# HyperRAM.net
KiCad netlist of a schematic drawn in Altium Designer
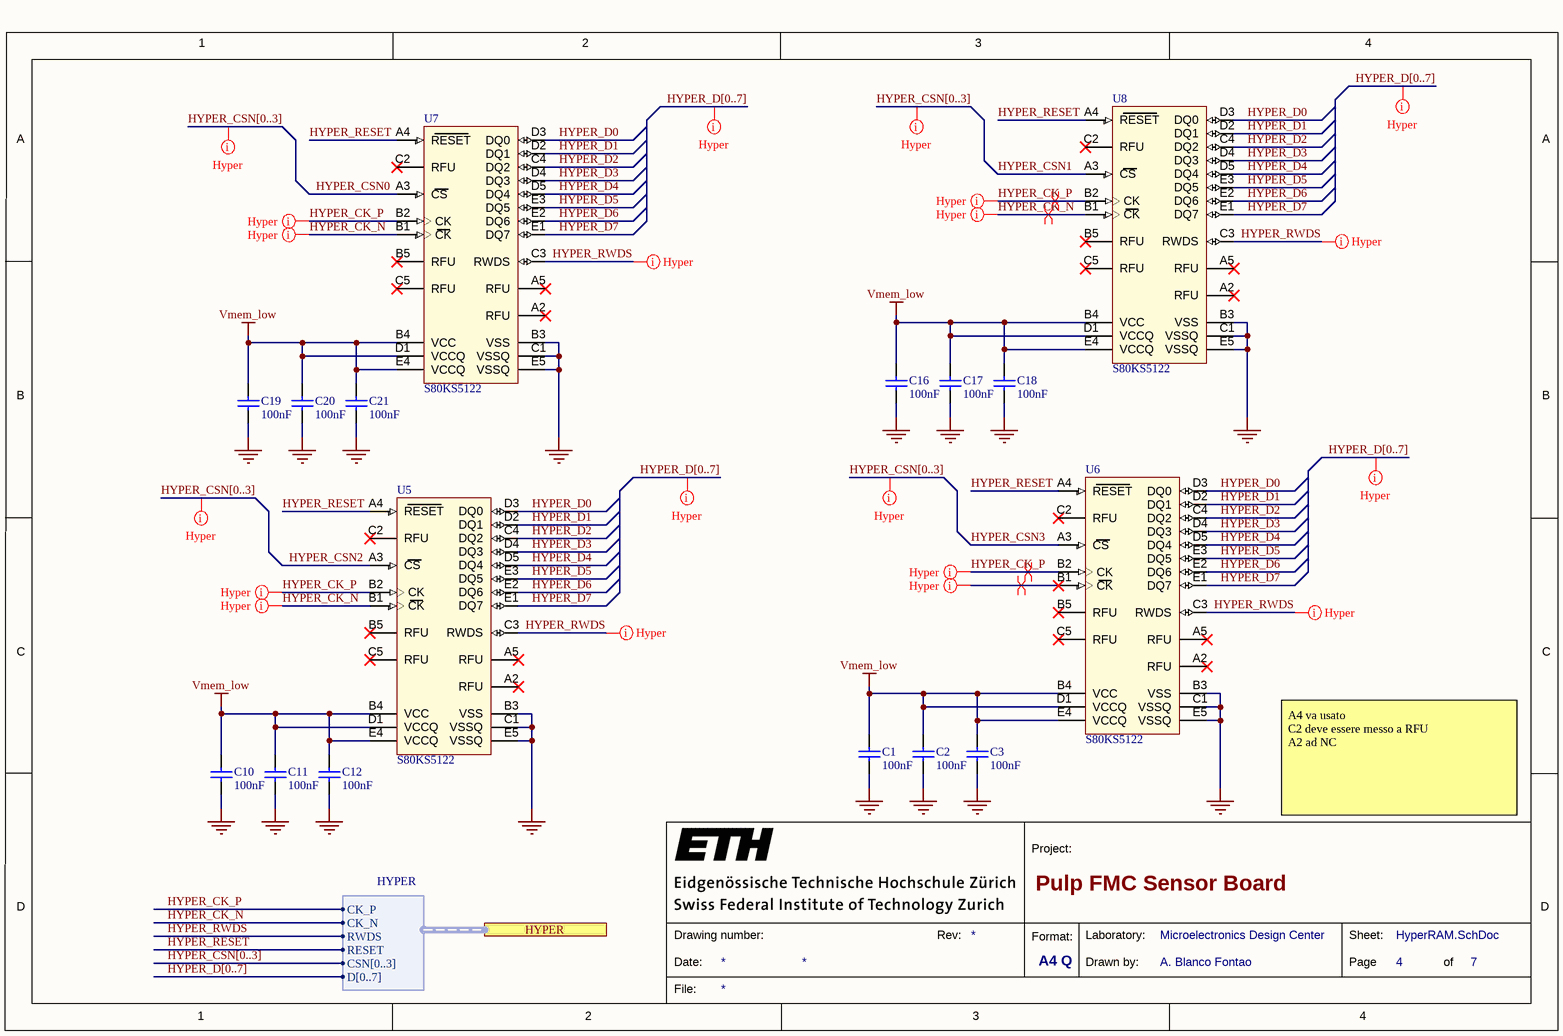
[diagram p0: HyperRAM.SchDoc]

(export (version "E")
  (design (tool "Eeschema 10.0.6"))
  (components
    (comp (ref "C1")
      (value "100nF")
      (footprint "CAPC0603(1608)100_N")
      (description "CAP 100nF 25V ±10% 0603 (1608 Metric) Thickness 1mm SMD")
      (fields (field (name "TOLERANCE") "Â±10%") (field (name "Comment") "CAP 100nF 25V 0603(1608)"))
      (libsource (lib "Altium Content Vault") (part "CMP-1035-02588-1"))
    )
    (comp (ref "C2")
      (value "100nF")
      (footprint "CAPC0603(1608)100_N")
      (description "CAP 100nF 25V ±10% 0603 (1608 Metric) Thickness 1mm SMD")
      (fields (field (name "TOLERANCE") "Â±10%") (field (name "Comment") "CAP 100nF 25V 0603(1608)"))
      (libsource (lib "Altium Content Vault") (part "CMP-1035-02588-1"))
    )
    (comp (ref "C3")
      (value "100nF")
      (footprint "CAPC0603(1608)100_N")
      (description "CAP 100nF 25V ±10% 0603 (1608 Metric) Thickness 1mm SMD")
      (fields (field (name "TOLERANCE") "Â±10%") (field (name "Comment") "CAP 100nF 25V 0603(1608)"))
      (libsource (lib "Altium Content Vault") (part "CMP-1035-02588-1"))
    )
    (comp (ref "C10")
      (value "100nF")
      (footprint "CAPC0603(1608)100_N")
      (description "CAP 100nF 25V ±10% 0603 (1608 Metric) Thickness 1mm SMD")
      (fields (field (name "TOLERANCE") "Â±10%") (field (name "Comment") "CAP 100nF 25V 0603(1608)"))
      (libsource (lib "Altium Content Vault") (part "CMP-1035-02588-1"))
    )
    (comp (ref "C11")
      (value "100nF")
      (footprint "CAPC0603(1608)100_N")
      (description "CAP 100nF 25V ±10% 0603 (1608 Metric) Thickness 1mm SMD")
      (fields (field (name "TOLERANCE") "Â±10%") (field (name "Comment") "CAP 100nF 25V 0603(1608)"))
      (libsource (lib "Altium Content Vault") (part "CMP-1035-02588-1"))
    )
    (comp (ref "C12")
      (value "100nF")
      (footprint "CAPC0603(1608)100_N")
      (description "CAP 100nF 25V ±10% 0603 (1608 Metric) Thickness 1mm SMD")
      (fields (field (name "TOLERANCE") "Â±10%") (field (name "Comment") "CAP 100nF 25V 0603(1608)"))
      (libsource (lib "Altium Content Vault") (part "CMP-1035-02588-1"))
    )
    (comp (ref "C16")
      (value "100nF")
      (footprint "CAPC0603(1608)100_N")
      (description "CAP 100nF 25V ±10% 0603 (1608 Metric) Thickness 1mm SMD")
      (fields (field (name "TOLERANCE") "Â±10%") (field (name "Comment") "CAP 100nF 25V 0603(1608)"))
      (libsource (lib "Altium Content Vault") (part "CMP-1035-02588-1"))
    )
    (comp (ref "C17")
      (value "100nF")
      (footprint "CAPC0603(1608)100_N")
      (description "CAP 100nF 25V ±10% 0603 (1608 Metric) Thickness 1mm SMD")
      (fields (field (name "TOLERANCE") "Â±10%") (field (name "Comment") "CAP 100nF 25V 0603(1608)"))
      (libsource (lib "Altium Content Vault") (part "CMP-1035-02588-1"))
    )
    (comp (ref "C18")
      (value "100nF")
      (footprint "CAPC0603(1608)100_N")
      (description "CAP 100nF 25V ±10% 0603 (1608 Metric) Thickness 1mm SMD")
      (fields (field (name "TOLERANCE") "Â±10%") (field (name "Comment") "CAP 100nF 25V 0603(1608)"))
      (libsource (lib "Altium Content Vault") (part "CMP-1035-02588-1"))
    )
    (comp (ref "C19")
      (value "100nF")
      (footprint "CAPC0603(1608)100_N")
      (description "CAP 100nF 25V ±10% 0603 (1608 Metric) Thickness 1mm SMD")
      (fields (field (name "TOLERANCE") "Â±10%") (field (name "Comment") "CAP 100nF 25V 0603(1608)"))
      (libsource (lib "Altium Content Vault") (part "CMP-1035-02588-1"))
    )
    (comp (ref "C20")
      (value "100nF")
      (footprint "CAPC0603(1608)100_N")
      (description "CAP 100nF 25V ±10% 0603 (1608 Metric) Thickness 1mm SMD")
      (fields (field (name "TOLERANCE") "Â±10%") (field (name "Comment") "CAP 100nF 25V 0603(1608)"))
      (libsource (lib "Altium Content Vault") (part "CMP-1035-02588-1"))
    )
    (comp (ref "C21")
      (value "100nF")
      (footprint "CAPC0603(1608)100_N")
      (description "CAP 100nF 25V ±10% 0603 (1608 Metric) Thickness 1mm SMD")
      (fields (field (name "TOLERANCE") "Â±10%") (field (name "Comment") "CAP 100nF 25V 0603(1608)"))
      (libsource (lib "Altium Content Vault") (part "CMP-1035-02588-1"))
    )
    (comp (ref "U5")
      (value "S80KS5122")
      (footprint "FBGA24_A-130")
      (description "512 Mb: HYPERRAM™ self-refresh dynamic\r\nRAM (DRAM) with HYPERBUS™ interface\r\n1.8 V")
      (libsource (lib "hyperRAM") (part "S80KS5122"))
    )
    (comp (ref "U6")
      (value "S80KS5122")
      (footprint "FBGA24_A-130")
      (description "512 Mb: HYPERRAM™ self-refresh dynamic\r\nRAM (DRAM) with HYPERBUS™ interface\r\n1.8 V")
      (libsource (lib "hyperRAM") (part "S80KS5122"))
    )
    (comp (ref "U7")
      (value "S80KS5122")
      (footprint "FBGA24_A-130")
      (description "512 Mb: HYPERRAM™ self-refresh dynamic\r\nRAM (DRAM) with HYPERBUS™ interface\r\n1.8 V")
      (libsource (lib "hyperRAM") (part "S80KS5122"))
    )
    (comp (ref "U8")
      (value "S80KS5122")
      (footprint "FBGA24_A-130")
      (description "512 Mb: HYPERRAM™ self-refresh dynamic\r\nRAM (DRAM) with HYPERBUS™ interface\r\n1.8 V")
      (libsource (lib "hyperRAM") (part "S80KS5122"))
    )
  )
  (nets
    (net (code "2") (name "/HYPER_CK_N") (class "Default")
      (node (ref "U5") (pin "B1") (pinfunction "CK_B1") (pintype "input"))
      (node (ref "U7") (pin "B1") (pinfunction "CK_B1") (pintype "input"))
      (node (ref "U8") (pin "B1") (pinfunction "CK_B1") (pintype "input"))
    )
    (net (code "3") (name "/HYPER_CK_P") (class "Default")
      (node (ref "U5") (pin "B2") (pinfunction "CK_B2") (pintype "input"))
      (node (ref "U6") (pin "B2") (pinfunction "CK_B2") (pintype "input"))
      (node (ref "U7") (pin "B2") (pinfunction "CK_B2") (pintype "input"))
      (node (ref "U8") (pin "B2") (pinfunction "CK_B2") (pintype "input"))
    )
    (net (code "4") (name "/HYPER_CSN0") (class "Default")
      (node (ref "U7") (pin "A3") (pinfunction "CS_A3") (pintype "input"))
    )
    (net (code "5") (name "/HYPER_CSN1") (class "Default")
      (node (ref "U8") (pin "A3") (pinfunction "CS_A3") (pintype "input"))
    )
    (net (code "6") (name "/HYPER_CSN2") (class "Default")
      (node (ref "U5") (pin "A3") (pinfunction "CS_A3") (pintype "input"))
    )
    (net (code "7") (name "/HYPER_CSN3") (class "Default")
      (node (ref "U6") (pin "A3") (pinfunction "CS_A3") (pintype "input"))
    )
    (net (code "9") (name "/HYPER_D0") (class "Default")
      (node (ref "U5") (pin "D3") (pinfunction "DQ0_D3") (pintype "bidirectional"))
      (node (ref "U6") (pin "D3") (pinfunction "DQ0_D3") (pintype "bidirectional"))
      (node (ref "U7") (pin "D3") (pinfunction "DQ0_D3") (pintype "bidirectional"))
      (node (ref "U8") (pin "D3") (pinfunction "DQ0_D3") (pintype "bidirectional"))
    )
    (net (code "10") (name "/HYPER_D1") (class "Default")
      (node (ref "U5") (pin "D2") (pinfunction "DQ1_D2") (pintype "bidirectional"))
      (node (ref "U6") (pin "D2") (pinfunction "DQ1_D2") (pintype "bidirectional"))
      (node (ref "U7") (pin "D2") (pinfunction "DQ1_D2") (pintype "bidirectional"))
      (node (ref "U8") (pin "D2") (pinfunction "DQ1_D2") (pintype "bidirectional"))
    )
    (net (code "11") (name "/HYPER_D2") (class "Default")
      (node (ref "U5") (pin "C4") (pinfunction "DQ2_C4") (pintype "bidirectional"))
      (node (ref "U6") (pin "C4") (pinfunction "DQ2_C4") (pintype "bidirectional"))
      (node (ref "U7") (pin "C4") (pinfunction "DQ2_C4") (pintype "bidirectional"))
      (node (ref "U8") (pin "C4") (pinfunction "DQ2_C4") (pintype "bidirectional"))
    )
    (net (code "12") (name "/HYPER_D3") (class "Default")
      (node (ref "U5") (pin "D4") (pinfunction "DQ3_D4") (pintype "bidirectional"))
      (node (ref "U6") (pin "D4") (pinfunction "DQ3_D4") (pintype "bidirectional"))
      (node (ref "U7") (pin "D4") (pinfunction "DQ3_D4") (pintype "bidirectional"))
      (node (ref "U8") (pin "D4") (pinfunction "DQ3_D4") (pintype "bidirectional"))
    )
    (net (code "13") (name "/HYPER_D4") (class "Default")
      (node (ref "U5") (pin "D5") (pinfunction "DQ4_D5") (pintype "bidirectional"))
      (node (ref "U6") (pin "D5") (pinfunction "DQ4_D5") (pintype "bidirectional"))
      (node (ref "U7") (pin "D5") (pinfunction "DQ4_D5") (pintype "bidirectional"))
      (node (ref "U8") (pin "D5") (pinfunction "DQ4_D5") (pintype "bidirectional"))
    )
    (net (code "14") (name "/HYPER_D5") (class "Default")
      (node (ref "U5") (pin "E3") (pinfunction "DQ5_E3") (pintype "bidirectional"))
      (node (ref "U6") (pin "E3") (pinfunction "DQ5_E3") (pintype "bidirectional"))
      (node (ref "U7") (pin "E3") (pinfunction "DQ5_E3") (pintype "bidirectional"))
      (node (ref "U8") (pin "E3") (pinfunction "DQ5_E3") (pintype "bidirectional"))
    )
    (net (code "15") (name "/HYPER_D6") (class "Default")
      (node (ref "U5") (pin "E2") (pinfunction "DQ6_E2") (pintype "bidirectional"))
      (node (ref "U6") (pin "E2") (pinfunction "DQ6_E2") (pintype "bidirectional"))
      (node (ref "U7") (pin "E2") (pinfunction "DQ6_E2") (pintype "bidirectional"))
      (node (ref "U8") (pin "E2") (pinfunction "DQ6_E2") (pintype "bidirectional"))
    )
    (net (code "16") (name "/HYPER_D7") (class "Default")
      (node (ref "U5") (pin "E1") (pinfunction "DQ7_E1") (pintype "bidirectional"))
      (node (ref "U6") (pin "E1") (pinfunction "DQ7_E1") (pintype "bidirectional"))
      (node (ref "U7") (pin "E1") (pinfunction "DQ7_E1") (pintype "bidirectional"))
      (node (ref "U8") (pin "E1") (pinfunction "DQ7_E1") (pintype "bidirectional"))
    )
    (net (code "18") (name "/HYPER_RESET") (class "Default")
      (node (ref "U5") (pin "A4") (pinfunction "RESET_A4") (pintype "input"))
      (node (ref "U6") (pin "A4") (pinfunction "RESET_A4") (pintype "input"))
      (node (ref "U7") (pin "A4") (pinfunction "RESET_A4") (pintype "input"))
      (node (ref "U8") (pin "A4") (pinfunction "RESET_A4") (pintype "input"))
    )
    (net (code "19") (name "/HYPER_RWDS") (class "Default")
      (node (ref "U5") (pin "C3") (pinfunction "RWDS_C3") (pintype "bidirectional"))
      (node (ref "U6") (pin "C3") (pinfunction "RWDS_C3") (pintype "bidirectional"))
      (node (ref "U7") (pin "C3") (pinfunction "RWDS_C3") (pintype "bidirectional"))
      (node (ref "U8") (pin "C3") (pinfunction "RWDS_C3") (pintype "bidirectional"))
    )
    (net (code "21") (name "GND") (class "Default")
      (node (ref "C1") (pin "1") (pinfunction "1_1") (pintype "passive"))
      (node (ref "C10") (pin "1") (pinfunction "1_1") (pintype "passive"))
      (node (ref "C11") (pin "1") (pinfunction "1_1") (pintype "passive"))
      (node (ref "C12") (pin "1") (pinfunction "1_1") (pintype "passive"))
      (node (ref "C16") (pin "1") (pinfunction "1_1") (pintype "passive"))
      (node (ref "C17") (pin "1") (pinfunction "1_1") (pintype "passive"))
      (node (ref "C18") (pin "1") (pinfunction "1_1") (pintype "passive"))
      (node (ref "C19") (pin "1") (pinfunction "1_1") (pintype "passive"))
      (node (ref "C2") (pin "1") (pinfunction "1_1") (pintype "passive"))
      (node (ref "C20") (pin "1") (pinfunction "1_1") (pintype "passive"))
      (node (ref "C21") (pin "1") (pinfunction "1_1") (pintype "passive"))
      (node (ref "C3") (pin "1") (pinfunction "1_1") (pintype "passive"))
      (node (ref "U5") (pin "B3") (pinfunction "VSS_B3") (pintype "passive"))
      (node (ref "U5") (pin "C1") (pinfunction "VSSQ_C1") (pintype "passive"))
      (node (ref "U5") (pin "E5") (pinfunction "VSSQ_E5") (pintype "passive"))
      (node (ref "U6") (pin "B3") (pinfunction "VSS_B3") (pintype "passive"))
      (node (ref "U6") (pin "C1") (pinfunction "VSSQ_C1") (pintype "passive"))
      (node (ref "U6") (pin "E5") (pinfunction "VSSQ_E5") (pintype "passive"))
      (node (ref "U7") (pin "B3") (pinfunction "VSS_B3") (pintype "passive"))
      (node (ref "U7") (pin "C1") (pinfunction "VSSQ_C1") (pintype "passive"))
      (node (ref "U7") (pin "E5") (pinfunction "VSSQ_E5") (pintype "passive"))
      (node (ref "U8") (pin "B3") (pinfunction "VSS_B3") (pintype "passive"))
      (node (ref "U8") (pin "C1") (pinfunction "VSSQ_C1") (pintype "passive"))
      (node (ref "U8") (pin "E5") (pinfunction "VSSQ_E5") (pintype "passive"))
    )
    (net (code "22") (name "Vmem_low") (class "Default")
      (node (ref "C1") (pin "2") (pinfunction "2_2") (pintype "passive"))
      (node (ref "C10") (pin "2") (pinfunction "2_2") (pintype "passive"))
      (node (ref "C11") (pin "2") (pinfunction "2_2") (pintype "passive"))
      (node (ref "C12") (pin "2") (pinfunction "2_2") (pintype "passive"))
      (node (ref "C16") (pin "2") (pinfunction "2_2") (pintype "passive"))
      (node (ref "C17") (pin "2") (pinfunction "2_2") (pintype "passive"))
      (node (ref "C18") (pin "2") (pinfunction "2_2") (pintype "passive"))
      (node (ref "C19") (pin "2") (pinfunction "2_2") (pintype "passive"))
      (node (ref "C2") (pin "2") (pinfunction "2_2") (pintype "passive"))
      (node (ref "C20") (pin "2") (pinfunction "2_2") (pintype "passive"))
      (node (ref "C21") (pin "2") (pinfunction "2_2") (pintype "passive"))
      (node (ref "C3") (pin "2") (pinfunction "2_2") (pintype "passive"))
      (node (ref "U5") (pin "B4") (pinfunction "VCC_B4") (pintype "passive"))
      (node (ref "U5") (pin "D1") (pinfunction "VCCQ_D1") (pintype "passive"))
      (node (ref "U5") (pin "E4") (pinfunction "VCCQ_E4") (pintype "passive"))
      (node (ref "U6") (pin "B4") (pinfunction "VCC_B4") (pintype "passive"))
      (node (ref "U6") (pin "D1") (pinfunction "VCCQ_D1") (pintype "passive"))
      (node (ref "U6") (pin "E4") (pinfunction "VCCQ_E4") (pintype "passive"))
      (node (ref "U7") (pin "B4") (pinfunction "VCC_B4") (pintype "passive"))
      (node (ref "U7") (pin "D1") (pinfunction "VCCQ_D1") (pintype "passive"))
      (node (ref "U7") (pin "E4") (pinfunction "VCCQ_E4") (pintype "passive"))
      (node (ref "U8") (pin "B4") (pinfunction "VCC_B4") (pintype "passive"))
      (node (ref "U8") (pin "D1") (pinfunction "VCCQ_D1") (pintype "passive"))
      (node (ref "U8") (pin "E4") (pinfunction "VCCQ_E4") (pintype "passive"))
    )
    (net (code "23") (name "unconnected-(U5-RFU-PadA2)") (class "Default")
      (node (ref "U5") (pin "A2") (pinfunction "RFU_A2") (pintype "passive+no_connect"))
    )
    (net (code "24") (name "unconnected-(U5-RFU-PadA5)") (class "Default")
      (node (ref "U5") (pin "A5") (pinfunction "RFU_A5") (pintype "passive+no_connect"))
    )
    (net (code "25") (name "unconnected-(U5-RFU-PadB5)") (class "Default")
      (node (ref "U5") (pin "B5") (pinfunction "RFU_B5") (pintype "passive+no_connect"))
    )
    (net (code "26") (name "unconnected-(U5-RFU-PadC2)") (class "Default")
      (node (ref "U5") (pin "C2") (pinfunction "RFU_C2") (pintype "passive+no_connect"))
    )
    (net (code "27") (name "unconnected-(U5-RFU-PadC5)") (class "Default")
      (node (ref "U5") (pin "C5") (pinfunction "RFU_C5") (pintype "passive+no_connect"))
    )
    (net (code "28") (name "unconnected-(U6-CK-PadB1)") (class "Default")
      (node (ref "U6") (pin "B1") (pinfunction "CK_B1") (pintype "input+no_connect"))
    )
    (net (code "29") (name "unconnected-(U6-RFU-PadA2)") (class "Default")
      (node (ref "U6") (pin "A2") (pinfunction "RFU_A2") (pintype "passive+no_connect"))
    )
    (net (code "30") (name "unconnected-(U6-RFU-PadA5)") (class "Default")
      (node (ref "U6") (pin "A5") (pinfunction "RFU_A5") (pintype "passive+no_connect"))
    )
    (net (code "31") (name "unconnected-(U6-RFU-PadB5)") (class "Default")
      (node (ref "U6") (pin "B5") (pinfunction "RFU_B5") (pintype "passive+no_connect"))
    )
    (net (code "32") (name "unconnected-(U6-RFU-PadC2)") (class "Default")
      (node (ref "U6") (pin "C2") (pinfunction "RFU_C2") (pintype "passive+no_connect"))
    )
    (net (code "33") (name "unconnected-(U6-RFU-PadC5)") (class "Default")
      (node (ref "U6") (pin "C5") (pinfunction "RFU_C5") (pintype "passive+no_connect"))
    )
    (net (code "34") (name "unconnected-(U7-RFU-PadA2)") (class "Default")
      (node (ref "U7") (pin "A2") (pinfunction "RFU_A2") (pintype "passive+no_connect"))
    )
    (net (code "35") (name "unconnected-(U7-RFU-PadA5)") (class "Default")
      (node (ref "U7") (pin "A5") (pinfunction "RFU_A5") (pintype "passive+no_connect"))
    )
    (net (code "36") (name "unconnected-(U7-RFU-PadB5)") (class "Default")
      (node (ref "U7") (pin "B5") (pinfunction "RFU_B5") (pintype "passive+no_connect"))
    )
    (net (code "37") (name "unconnected-(U7-RFU-PadC2)") (class "Default")
      (node (ref "U7") (pin "C2") (pinfunction "RFU_C2") (pintype "passive+no_connect"))
    )
    (net (code "38") (name "unconnected-(U7-RFU-PadC5)") (class "Default")
      (node (ref "U7") (pin "C5") (pinfunction "RFU_C5") (pintype "passive+no_connect"))
    )
    (net (code "39") (name "unconnected-(U8-RFU-PadA2)") (class "Default")
      (node (ref "U8") (pin "A2") (pinfunction "RFU_A2") (pintype "passive+no_connect"))
    )
    (net (code "40") (name "unconnected-(U8-RFU-PadA5)") (class "Default")
      (node (ref "U8") (pin "A5") (pinfunction "RFU_A5") (pintype "passive+no_connect"))
    )
    (net (code "41") (name "unconnected-(U8-RFU-PadB5)") (class "Default")
      (node (ref "U8") (pin "B5") (pinfunction "RFU_B5") (pintype "passive+no_connect"))
    )
    (net (code "42") (name "unconnected-(U8-RFU-PadC2)") (class "Default")
      (node (ref "U8") (pin "C2") (pinfunction "RFU_C2") (pintype "passive+no_connect"))
    )
    (net (code "43") (name "unconnected-(U8-RFU-PadC5)") (class "Default")
      (node (ref "U8") (pin "C5") (pinfunction "RFU_C5") (pintype "passive+no_connect"))
    )
  )
)
